# IRsender.net
KiCad netlist of a schematic drawn in EAGLE
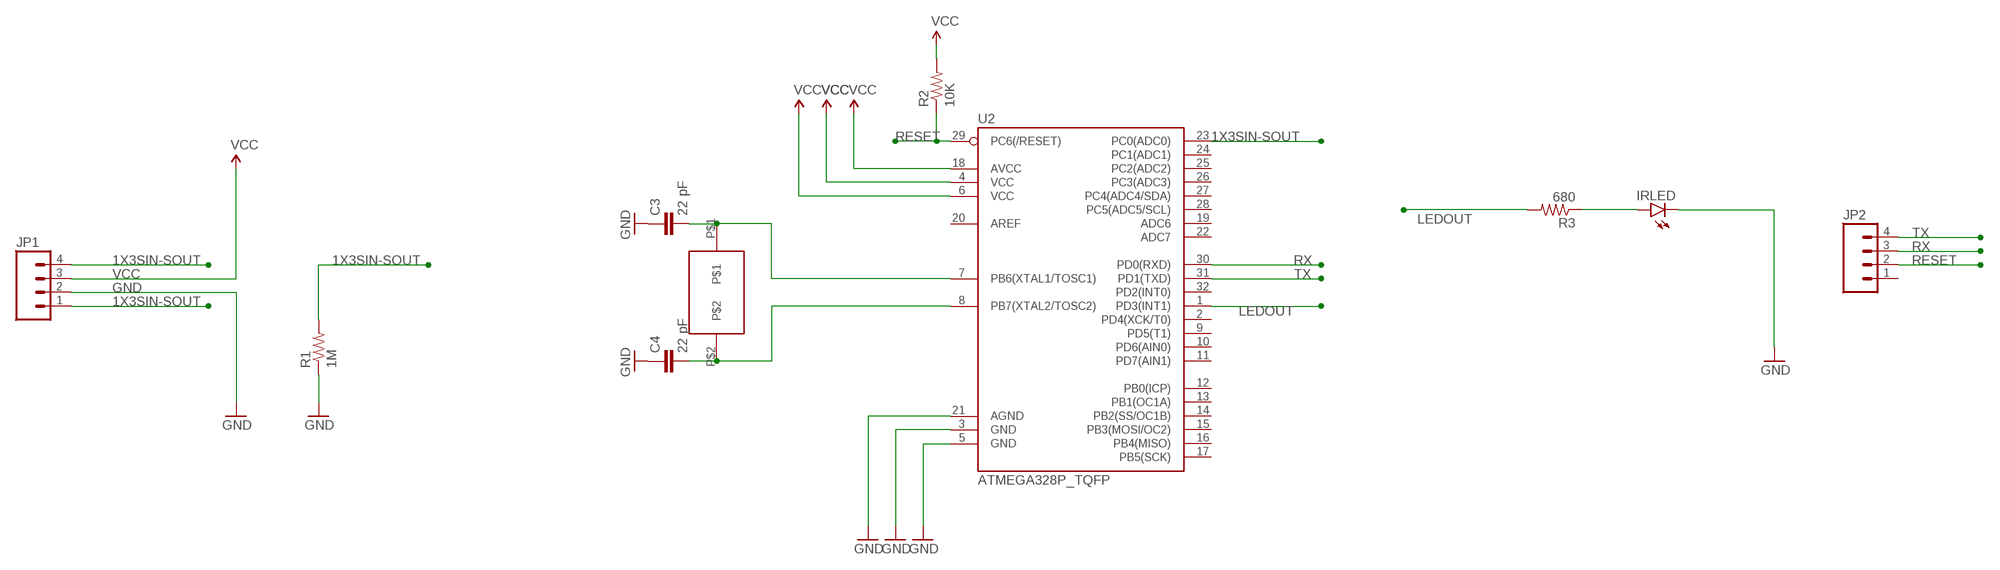
[diagram p0: schematic, sheet 1]

(export (version "E")
  (design (tool "Eeschema 10.0.6"))
  (components
    (comp (ref "C3")
      (value "22 pF")
      (footprint "eagle-import:0603-CAP")
      (libsource (lib "eagle-import") (part "CAP0603-CAP"))
    )
    (comp (ref "C4")
      (value "22 pF")
      (footprint "eagle-import:0603-CAP")
      (libsource (lib "eagle-import") (part "CAP0603-CAP"))
    )
    (comp (ref "IRLED")
      (value "LED5MM")
      (footprint "eagle-import:LED5MM")
      (libsource (lib "eagle-import") (part "LED5MM"))
    )
    (comp (ref "JP1")
      (value "M04PTH")
      (footprint "eagle-import:1X04")
      (libsource (lib "eagle-import") (part "M04PTH"))
    )
    (comp (ref "JP2")
      (value "M04PTH")
      (footprint "eagle-import:1X04")
      (libsource (lib "eagle-import") (part "M04PTH"))
    )
    (comp (ref "R1")
      (value "1M")
      (footprint "eagle-import:R0603")
      (libsource (lib "eagle-import") (part "R-US_R0603"))
    )
    (comp (ref "R2")
      (value "10K")
      (footprint "eagle-import:R0603")
      (libsource (lib "eagle-import") (part "resistor_R-US_R0603"))
    )
    (comp (ref "R3")
      (value "680")
      (footprint "eagle-import:R0603")
      (libsource (lib "eagle-import") (part "R-US_R0603"))
    )
    (comp (ref "U$2")
      (value "NX503")
      (footprint "eagle-import:NX503")
      (libsource (lib "eagle-import") (part "NX503"))
    )
    (comp (ref "U2")
      (value "ATMEGA328P_TQFP")
      (footprint "eagle-import:TQFP32-08")
      (libsource (lib "eagle-import") (part "ATMEGA328P_TQFP"))
    )
  )
  (nets
    (net (code "1") (name "/1X3SIN-SOUT") (class "Default")
      (node (ref "JP1") (pin "1") (pinfunction "1_1") (pintype "passive"))
      (node (ref "JP1") (pin "4") (pinfunction "4_4") (pintype "passive"))
      (node (ref "R1") (pin "2") (pinfunction "2_2") (pintype "passive"))
      (node (ref "U2") (pin "23") (pinfunction "PC0(ADC0)_23") (pintype "bidirectional"))
    )
    (net (code "2") (name "/LEDOUT") (class "Default")
      (node (ref "R3") (pin "2") (pinfunction "2_2") (pintype "passive"))
      (node (ref "U2") (pin "1") (pinfunction "PD3(INT1)_1") (pintype "bidirectional"))
    )
    (net (code "3") (name "/RESET") (class "Default")
      (node (ref "JP2") (pin "2") (pinfunction "2_2") (pintype "passive"))
      (node (ref "R2") (pin "1") (pinfunction "1_1") (pintype "passive"))
      (node (ref "U2") (pin "29") (pinfunction "PC6(/RESET)_29") (pintype "bidirectional"))
    )
    (net (code "4") (name "/RX") (class "Default")
      (node (ref "JP2") (pin "3") (pinfunction "3_3") (pintype "passive"))
      (node (ref "U2") (pin "30") (pinfunction "PD0(RXD)_30") (pintype "bidirectional"))
    )
    (net (code "5") (name "/TX") (class "Default")
      (node (ref "JP2") (pin "4") (pinfunction "4_4") (pintype "passive"))
      (node (ref "U2") (pin "31") (pinfunction "PD1(TXD)_31") (pintype "bidirectional"))
    )
    (net (code "6") (name "GND") (class "Default")
      (node (ref "C3") (pin "1") (pinfunction "1_1") (pintype "passive"))
      (node (ref "C4") (pin "1") (pinfunction "1_1") (pintype "passive"))
      (node (ref "IRLED") (pin "K") (pinfunction "C_K") (pintype "passive"))
      (node (ref "JP1") (pin "2") (pinfunction "2_2") (pintype "passive"))
      (node (ref "R1") (pin "1") (pinfunction "1_1") (pintype "passive"))
      (node (ref "U2") (pin "21") (pinfunction "AGND_21") (pintype "bidirectional"))
      (node (ref "U2") (pin "3") (pinfunction "GND_3") (pintype "bidirectional"))
      (node (ref "U2") (pin "5") (pinfunction "GND_5") (pintype "bidirectional"))
    )
    (net (code "7") (name "Net-(IRLED-PadA)") (class "Default")
      (node (ref "IRLED") (pin "A") (pinfunction "A_A") (pintype "passive"))
      (node (ref "R3") (pin "1") (pinfunction "1_1") (pintype "passive"))
    )
    (net (code "8") (name "Net-(U2-PB6(XTAL1{slash}TOSC1))") (class "Default")
      (node (ref "C3") (pin "2") (pinfunction "2_2") (pintype "passive"))
      (node (ref "U$2") (pin "P$1") (pinfunction "P$1_P$1") (pintype "bidirectional"))
      (node (ref "U2") (pin "7") (pinfunction "PB6(XTAL1/TOSC1)_7") (pintype "bidirectional"))
    )
    (net (code "9") (name "Net-(U2-PB7(XTAL2{slash}TOSC2))") (class "Default")
      (node (ref "C4") (pin "2") (pinfunction "2_2") (pintype "passive"))
      (node (ref "U$2") (pin "P$2") (pinfunction "P$2_P$2") (pintype "bidirectional"))
      (node (ref "U2") (pin "8") (pinfunction "PB7(XTAL2/TOSC2)_8") (pintype "bidirectional"))
    )
    (net (code "10") (name "VCC") (class "Default")
      (node (ref "JP1") (pin "3") (pinfunction "3_3") (pintype "passive"))
      (node (ref "R2") (pin "2") (pinfunction "2_2") (pintype "passive"))
      (node (ref "U2") (pin "18") (pinfunction "AVCC_18") (pintype "bidirectional"))
      (node (ref "U2") (pin "4") (pinfunction "VCC_4") (pintype "bidirectional"))
      (node (ref "U2") (pin "6") (pinfunction "VCC_6") (pintype "bidirectional"))
    )
    (net (code "11") (name "unconnected-(JP2-Pad1)") (class "Default")
      (node (ref "JP2") (pin "1") (pinfunction "1_1") (pintype "passive"))
    )
    (net (code "12") (name "unconnected-(U2-ADC6-Pad19)") (class "Default")
      (node (ref "U2") (pin "19") (pinfunction "ADC6_19") (pintype "bidirectional"))
    )
    (net (code "13") (name "unconnected-(U2-ADC7-Pad22)") (class "Default")
      (node (ref "U2") (pin "22") (pinfunction "ADC7_22") (pintype "bidirectional"))
    )
    (net (code "14") (name "unconnected-(U2-AREF-Pad20)") (class "Default")
      (node (ref "U2") (pin "20") (pinfunction "AREF_20") (pintype "bidirectional"))
    )
    (net (code "15") (name "unconnected-(U2-PB0(ICP)-Pad12)") (class "Default")
      (node (ref "U2") (pin "12") (pinfunction "PB0(ICP)_12") (pintype "bidirectional"))
    )
    (net (code "16") (name "unconnected-(U2-PB1(OC1A)-Pad13)") (class "Default")
      (node (ref "U2") (pin "13") (pinfunction "PB1(OC1A)_13") (pintype "bidirectional"))
    )
    (net (code "17") (name "unconnected-(U2-PB2(SS{slash}OC1B)-Pad14)") (class "Default")
      (node (ref "U2") (pin "14") (pinfunction "PB2(SS/OC1B)_14") (pintype "bidirectional"))
    )
    (net (code "18") (name "unconnected-(U2-PB3(MOSI{slash}OC2)-Pad15)") (class "Default")
      (node (ref "U2") (pin "15") (pinfunction "PB3(MOSI/OC2)_15") (pintype "bidirectional"))
    )
    (net (code "19") (name "unconnected-(U2-PB4(MISO)-Pad16)") (class "Default")
      (node (ref "U2") (pin "16") (pinfunction "PB4(MISO)_16") (pintype "bidirectional"))
    )
    (net (code "20") (name "unconnected-(U2-PB5(SCK)-Pad17)") (class "Default")
      (node (ref "U2") (pin "17") (pinfunction "PB5(SCK)_17") (pintype "bidirectional"))
    )
    (net (code "21") (name "unconnected-(U2-PC1(ADC1)-Pad24)") (class "Default")
      (node (ref "U2") (pin "24") (pinfunction "PC1(ADC1)_24") (pintype "bidirectional"))
    )
    (net (code "22") (name "unconnected-(U2-PC2(ADC2)-Pad25)") (class "Default")
      (node (ref "U2") (pin "25") (pinfunction "PC2(ADC2)_25") (pintype "bidirectional"))
    )
    (net (code "23") (name "unconnected-(U2-PC3(ADC3)-Pad26)") (class "Default")
      (node (ref "U2") (pin "26") (pinfunction "PC3(ADC3)_26") (pintype "bidirectional"))
    )
    (net (code "24") (name "unconnected-(U2-PC4(ADC4{slash}SDA)-Pad27)") (class "Default")
      (node (ref "U2") (pin "27") (pinfunction "PC4(ADC4/SDA)_27") (pintype "bidirectional"))
    )
    (net (code "25") (name "unconnected-(U2-PC5(ADC5{slash}SCL)-Pad28)") (class "Default")
      (node (ref "U2") (pin "28") (pinfunction "PC5(ADC5/SCL)_28") (pintype "bidirectional"))
    )
    (net (code "26") (name "unconnected-(U2-PD2(INT0)-Pad32)") (class "Default")
      (node (ref "U2") (pin "32") (pinfunction "PD2(INT0)_32") (pintype "bidirectional"))
    )
    (net (code "27") (name "unconnected-(U2-PD4(XCK{slash}T0)-Pad2)") (class "Default")
      (node (ref "U2") (pin "2") (pinfunction "PD4(XCK/T0)_2") (pintype "bidirectional"))
    )
    (net (code "28") (name "unconnected-(U2-PD5(T1)-Pad9)") (class "Default")
      (node (ref "U2") (pin "9") (pinfunction "PD5(T1)_9") (pintype "bidirectional"))
    )
    (net (code "29") (name "unconnected-(U2-PD6(AIN0)-Pad10)") (class "Default")
      (node (ref "U2") (pin "10") (pinfunction "PD6(AIN0)_10") (pintype "bidirectional"))
    )
    (net (code "30") (name "unconnected-(U2-PD7(AIN1)-Pad11)") (class "Default")
      (node (ref "U2") (pin "11") (pinfunction "PD7(AIN1)_11") (pintype "bidirectional"))
    )
  )
)
